# DAC_Buffer_Filter.net
KiCad netlist of a schematic drawn in Altium Designer
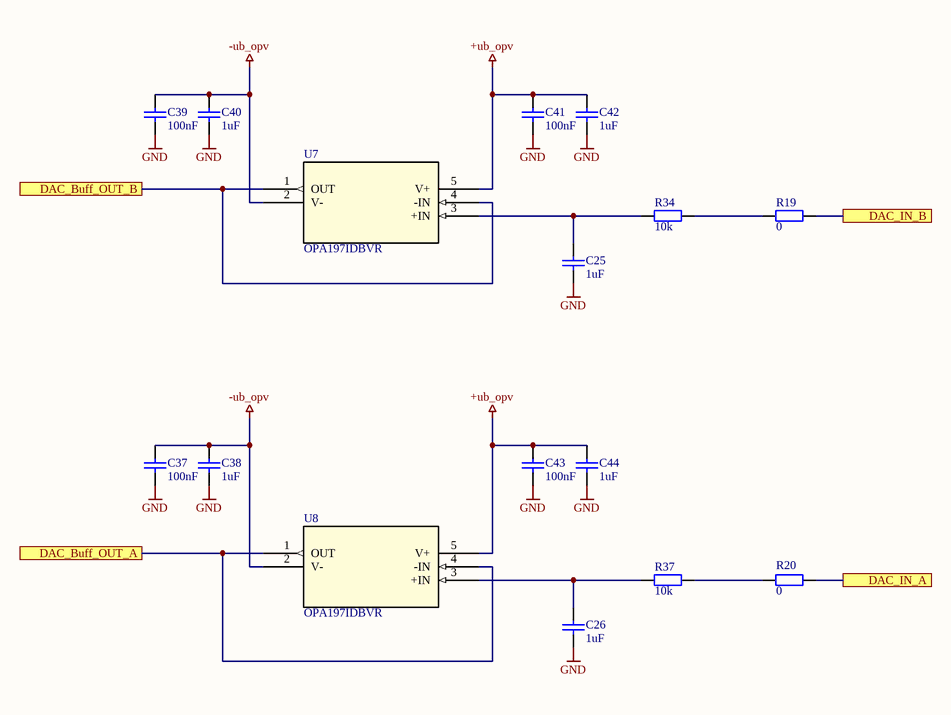
[diagram p0: DAC_Buffer_Filter.SchDoc]

(export (version "E")
  (design (tool "Eeschema 10.0.6"))
  (components
    (comp (ref "C25")
      (value "1uF")
      (footprint "C1206-KUE")
      (description "Capacitor")
      (fields (field (name "MANUFACTURER") "Kemet") (field (name "PUBLISHER") "Altium Limited"))
      (libsource (lib "ExtrapartsKUE_V01") (part "Capacitor"))
    )
    (comp (ref "C26")
      (value "1uF")
      (footprint "C1206-KUE")
      (description "Capacitor")
      (fields (field (name "MANUFACTURER") "Kemet") (field (name "PUBLISHER") "Altium Limited"))
      (libsource (lib "ExtrapartsKUE_V01") (part "Capacitor"))
    )
    (comp (ref "C37")
      (value "100nF")
      (footprint "C1206-KUE")
      (description "Capacitor")
      (fields (field (name "MANUFACTURER") "Kemet") (field (name "PUBLISHER") "Altium Limited"))
      (libsource (lib "ExtrapartsKUE_V01") (part "Capacitor"))
    )
    (comp (ref "C38")
      (value "1uF")
      (footprint "C1206-KUE")
      (description "Capacitor")
      (fields (field (name "MANUFACTURER") "Kemet") (field (name "PUBLISHER") "Altium Limited"))
      (libsource (lib "ExtrapartsKUE_V01") (part "Capacitor"))
    )
    (comp (ref "C39")
      (value "100nF")
      (footprint "C1206-KUE")
      (description "Capacitor")
      (fields (field (name "MANUFACTURER") "Kemet") (field (name "PUBLISHER") "Altium Limited"))
      (libsource (lib "ExtrapartsKUE_V01") (part "Capacitor"))
    )
    (comp (ref "C40")
      (value "1uF")
      (footprint "C1206-KUE")
      (description "Capacitor")
      (fields (field (name "MANUFACTURER") "Kemet") (field (name "PUBLISHER") "Altium Limited"))
      (libsource (lib "ExtrapartsKUE_V01") (part "Capacitor"))
    )
    (comp (ref "C41")
      (value "100nF")
      (footprint "C1206-KUE")
      (description "Capacitor")
      (fields (field (name "MANUFACTURER") "Kemet") (field (name "PUBLISHER") "Altium Limited"))
      (libsource (lib "ExtrapartsKUE_V01") (part "Capacitor"))
    )
    (comp (ref "C42")
      (value "1uF")
      (footprint "C1206-KUE")
      (description "Capacitor")
      (fields (field (name "MANUFACTURER") "Kemet") (field (name "PUBLISHER") "Altium Limited"))
      (libsource (lib "ExtrapartsKUE_V01") (part "Capacitor"))
    )
    (comp (ref "C43")
      (value "100nF")
      (footprint "C1206-KUE")
      (description "Capacitor")
      (fields (field (name "MANUFACTURER") "Kemet") (field (name "PUBLISHER") "Altium Limited"))
      (libsource (lib "ExtrapartsKUE_V01") (part "Capacitor"))
    )
    (comp (ref "C44")
      (value "1uF")
      (footprint "C1206-KUE")
      (description "Capacitor")
      (fields (field (name "MANUFACTURER") "Kemet") (field (name "PUBLISHER") "Altium Limited"))
      (libsource (lib "ExtrapartsKUE_V01") (part "Capacitor"))
    )
    (comp (ref "R19")
      (value "0")
      (footprint "C1206-KUE")
      (description "Resistor SMD")
      (fields (field (name "MANUFACTURER") "AVX") (field (name "PUBLISHER") "Altium Limited"))
      (libsource (lib "ExtrapartsKUE_V01") (part "ResistorSMD"))
    )
    (comp (ref "R20")
      (value "0")
      (footprint "C1206-KUE")
      (description "Resistor SMD")
      (fields (field (name "MANUFACTURER") "AVX") (field (name "PUBLISHER") "Altium Limited"))
      (libsource (lib "ExtrapartsKUE_V01") (part "ResistorSMD"))
    )
    (comp (ref "R34")
      (value "10k")
      (footprint "C1206-KUE")
      (description "Resistor SMD")
      (fields (field (name "MANUFACTURER") "AVX") (field (name "PUBLISHER") "Altium Limited"))
      (libsource (lib "ExtrapartsKUE_V01") (part "ResistorSMD"))
    )
    (comp (ref "R37")
      (value "10k")
      (footprint "C1206-KUE")
      (description "Resistor SMD")
      (fields (field (name "MANUFACTURER") "AVX") (field (name "PUBLISHER") "Altium Limited"))
      (libsource (lib "ExtrapartsKUE_V01") (part "ResistorSMD"))
    )
    (comp (ref "U7")
      (value "OPA197IDBVR")
      (footprint "DBV5_TEX")
      (description "Single, 36-V, precision, rail-to-rail input output, low offset voltage op amp 5-SOT-23 -40 to 125")
      (fields (field (name "COPYRIGHT") "Copyright (C) 2025 Ultra Librarian. All rights reserved."))
      (libsource (lib "OPA197IDBVR") (part "OPA197IDBVR"))
    )
    (comp (ref "U8")
      (value "OPA197IDBVR")
      (footprint "DBV5_TEX")
      (description "Single, 36-V, precision, rail-to-rail input output, low offset voltage op amp 5-SOT-23 -40 to 125")
      (fields (field (name "COPYRIGHT") "Copyright (C) 2025 Ultra Librarian. All rights reserved."))
      (libsource (lib "OPA197IDBVR") (part "OPA197IDBVR"))
    )
  )
  (nets
    (net (code "1") (name "+ub_opv") (class "Default")
      (node (ref "C41") (pin "2") (pinfunction "2_2") (pintype "passive"))
      (node (ref "C42") (pin "2") (pinfunction "2_2") (pintype "passive"))
      (node (ref "C43") (pin "2") (pinfunction "2_2") (pintype "passive"))
      (node (ref "C44") (pin "2") (pinfunction "2_2") (pintype "passive"))
      (node (ref "U7") (pin "5") (pinfunction "V+_5") (pintype "power_in"))
      (node (ref "U8") (pin "5") (pinfunction "V+_5") (pintype "power_in"))
    )
    (net (code "2") (name "-ub_opv") (class "Default")
      (node (ref "C37") (pin "2") (pinfunction "2_2") (pintype "passive"))
      (node (ref "C38") (pin "2") (pinfunction "2_2") (pintype "passive"))
      (node (ref "C39") (pin "2") (pinfunction "2_2") (pintype "passive"))
      (node (ref "C40") (pin "2") (pinfunction "2_2") (pintype "passive"))
      (node (ref "U7") (pin "2") (pinfunction "V-_2") (pintype "power_in"))
      (node (ref "U8") (pin "2") (pinfunction "V-_2") (pintype "power_in"))
    )
    (net (code "3") (name "/DAC_Buff_OUT_A") (class "Default")
      (node (ref "U8") (pin "1") (pinfunction "OUT_1") (pintype "output"))
      (node (ref "U8") (pin "4") (pinfunction "-IN_4") (pintype "input"))
    )
    (net (code "4") (name "/DAC_Buff_OUT_B") (class "Default")
      (node (ref "U7") (pin "1") (pinfunction "OUT_1") (pintype "output"))
      (node (ref "U7") (pin "4") (pinfunction "-IN_4") (pintype "input"))
    )
    (net (code "5") (name "/DAC_IN_A") (class "Default")
      (node (ref "R20") (pin "1") (pinfunction "1_1") (pintype "passive"))
    )
    (net (code "6") (name "/DAC_IN_B") (class "Default")
      (node (ref "R19") (pin "1") (pinfunction "1_1") (pintype "passive"))
    )
    (net (code "7") (name "GND") (class "Default")
      (node (ref "C25") (pin "1") (pinfunction "1_1") (pintype "passive"))
      (node (ref "C26") (pin "1") (pinfunction "1_1") (pintype "passive"))
      (node (ref "C37") (pin "1") (pinfunction "1_1") (pintype "passive"))
      (node (ref "C38") (pin "1") (pinfunction "1_1") (pintype "passive"))
      (node (ref "C39") (pin "1") (pinfunction "1_1") (pintype "passive"))
      (node (ref "C40") (pin "1") (pinfunction "1_1") (pintype "passive"))
      (node (ref "C41") (pin "1") (pinfunction "1_1") (pintype "passive"))
      (node (ref "C42") (pin "1") (pinfunction "1_1") (pintype "passive"))
      (node (ref "C43") (pin "1") (pinfunction "1_1") (pintype "passive"))
      (node (ref "C44") (pin "1") (pinfunction "1_1") (pintype "passive"))
    )
    (net (code "8") (name "Net-(R19-Pad2)") (class "Default")
      (node (ref "R19") (pin "2") (pinfunction "2_2") (pintype "passive"))
      (node (ref "R34") (pin "1") (pinfunction "1_1") (pintype "passive"))
    )
    (net (code "9") (name "Net-(R20-Pad2)") (class "Default")
      (node (ref "R20") (pin "2") (pinfunction "2_2") (pintype "passive"))
      (node (ref "R37") (pin "1") (pinfunction "1_1") (pintype "passive"))
    )
    (net (code "10") (name "Net-(U7-+IN)") (class "Default")
      (node (ref "C25") (pin "2") (pinfunction "2_2") (pintype "passive"))
      (node (ref "R34") (pin "2") (pinfunction "2_2") (pintype "passive"))
      (node (ref "U7") (pin "3") (pinfunction "+IN_3") (pintype "input"))
    )
    (net (code "11") (name "Net-(U8-+IN)") (class "Default")
      (node (ref "C26") (pin "2") (pinfunction "2_2") (pintype "passive"))
      (node (ref "R37") (pin "2") (pinfunction "2_2") (pintype "passive"))
      (node (ref "U8") (pin "3") (pinfunction "+IN_3") (pintype "input"))
    )
  )
)
